# 8_imu_debug_conn.net
KiCad netlist of a schematic drawn in Altium Designer
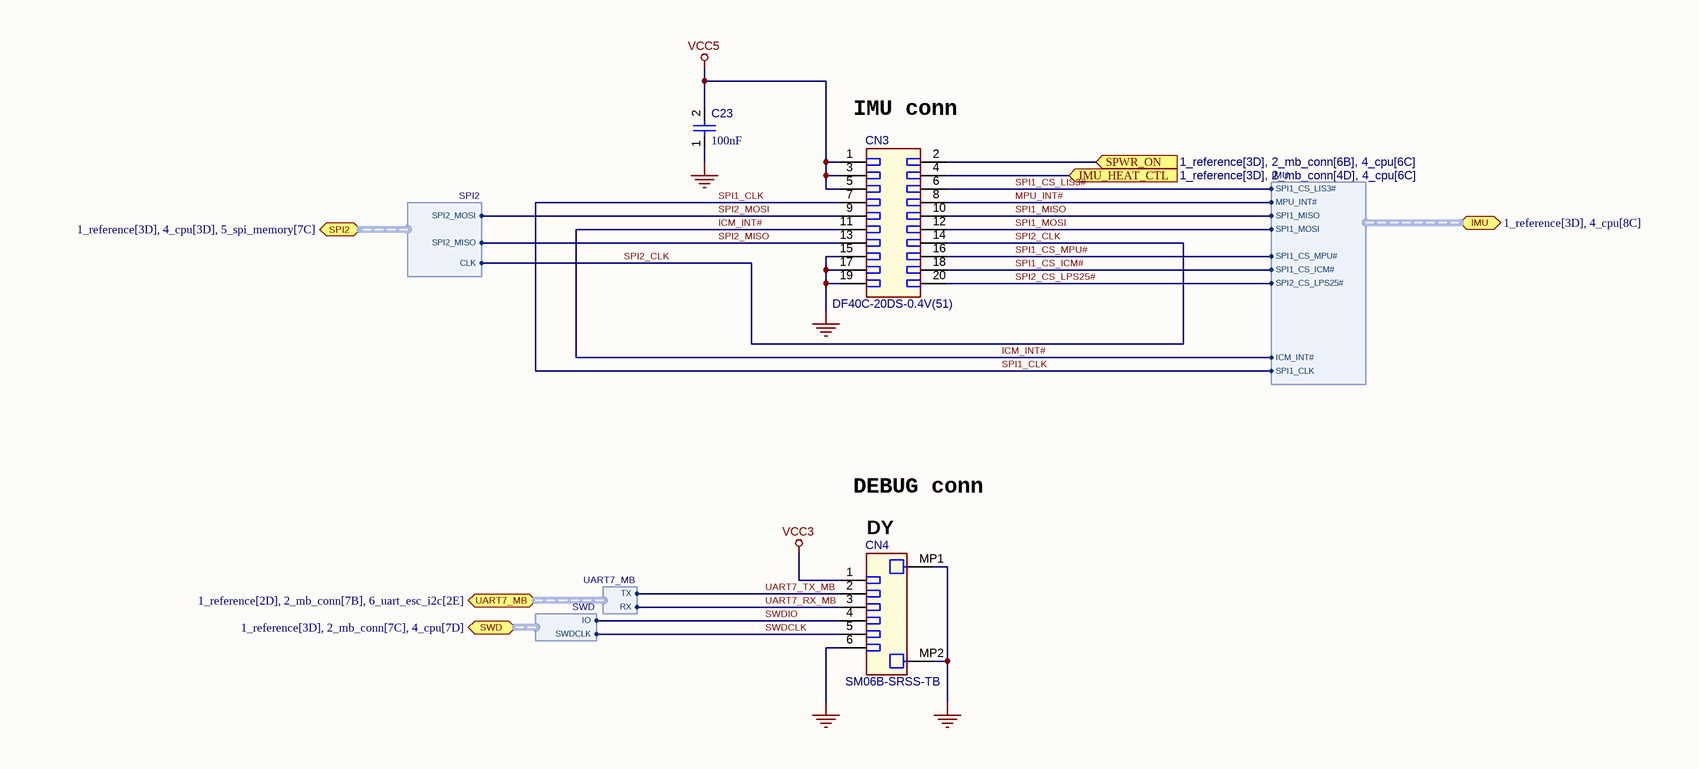
[diagram p0: 8_imu&debug_conn.SchDoc]

(export (version "E")
  (design (tool "Eeschema 10.0.6"))
  (components
    (comp (ref "C23")
      (value "100nF")
      (footprint "CAPC0402(1005)60_L")
      (description "Chip Capacitor, 100nF +/-20%, 10V, 0402, Thickness 0.6 mm")
      (fields (field (name "TOLERANCE") "20%") (field (name "Comment") "Capacitor 100nF +/-20% 10V 0402"))
      (libsource (lib "MHH -  Altium Advanced Course A365 01") (part "CAP-NP-2"))
    )
    (comp (ref "CN3")
      (value "DF40C-20DS-0.4V(51)")
      (footprint "HIRO-DF40C-20DS-0.4V(51)_V")
      (description "Receptacle Connector, 30 V, 0.3 A, -35 to 85 degC, RoHS, Tape and Reel")
      (libsource (lib "MHH -  Altium Advanced Course A365 01") (part "CMP-00114-7"))
    )
    (comp (ref "CN4")
      (value "SM06B-SRSS-TB")
      (footprint "JST-SM06B-SRSS-TB_V")
      (description "Male Header, Pitch 1 mm, 1 x 6 Position, Height 2.95 mm, -25 to 85 degC, RoHS, Tape and Reel")
      (libsource (lib "MHH -  Altium Advanced Course A365 01") (part "CMP-00143-5"))
    )
  )
  (nets
    (net (code "5") (name "/ICM_INT#") (class "Default")
      (node (ref "CN3") (pin "11") (pinfunction "11_11") (pintype "passive"))
    )
    (net (code "6") (name "/IMU_HEAT_CTL") (class "Default")
      (node (ref "CN3") (pin "4") (pinfunction "4_4") (pintype "passive"))
    )
    (net (code "7") (name "/MPU_INT#") (class "Default")
      (node (ref "CN3") (pin "8") (pinfunction "8_8") (pintype "passive"))
    )
    (net (code "8") (name "/SPI1_CLK") (class "Default")
      (node (ref "CN3") (pin "7") (pinfunction "7_7") (pintype "passive"))
    )
    (net (code "9") (name "/SPI1_CS_ICM#") (class "Default")
      (node (ref "CN3") (pin "18") (pinfunction "18_18") (pintype "passive"))
    )
    (net (code "10") (name "/SPI1_CS_LIS3#") (class "Default")
      (node (ref "CN3") (pin "6") (pinfunction "6_6") (pintype "passive"))
    )
    (net (code "11") (name "/SPI1_CS_MPU#") (class "Default")
      (node (ref "CN3") (pin "16") (pinfunction "16_16") (pintype "passive"))
    )
    (net (code "12") (name "/SPI1_MISO") (class "Default")
      (node (ref "CN3") (pin "10") (pinfunction "10_10") (pintype "passive"))
    )
    (net (code "13") (name "/SPI1_MOSI") (class "Default")
      (node (ref "CN3") (pin "12") (pinfunction "12_12") (pintype "passive"))
    )
    (net (code "14") (name "/SPI2_CLK") (class "Default")
      (node (ref "CN3") (pin "14") (pinfunction "14_14") (pintype "passive"))
    )
    (net (code "15") (name "/SPI2_CS_LPS25#") (class "Default")
      (node (ref "CN3") (pin "20") (pinfunction "20_20") (pintype "passive"))
    )
    (net (code "16") (name "/SPI2_MISO") (class "Default")
      (node (ref "CN3") (pin "13") (pinfunction "13_13") (pintype "passive"))
    )
    (net (code "17") (name "/SPI2_MOSI") (class "Default")
      (node (ref "CN3") (pin "9") (pinfunction "9_9") (pintype "passive"))
    )
    (net (code "18") (name "/SPWR_ON") (class "Default")
      (node (ref "CN3") (pin "2") (pinfunction "2_2") (pintype "passive"))
    )
    (net (code "19") (name "/SWDCLK") (class "Default")
      (node (ref "CN4") (pin "5") (pinfunction "5_5") (pintype "passive"))
    )
    (net (code "20") (name "/SWDIO") (class "Default")
      (node (ref "CN4") (pin "4") (pinfunction "4_4") (pintype "passive"))
    )
    (net (code "21") (name "/UART7_RX_MB") (class "Default")
      (node (ref "CN4") (pin "3") (pinfunction "3_3") (pintype "passive"))
    )
    (net (code "22") (name "/UART7_TX_MB") (class "Default")
      (node (ref "CN4") (pin "2") (pinfunction "2_2") (pintype "passive"))
    )
    (net (code "27") (name "GND") (class "Default")
      (node (ref "C23") (pin "1") (pinfunction "1_1") (pintype "passive"))
      (node (ref "CN3") (pin "15") (pinfunction "15_15") (pintype "passive"))
      (node (ref "CN3") (pin "17") (pinfunction "17_17") (pintype "passive"))
      (node (ref "CN3") (pin "19") (pinfunction "19_19") (pintype "passive"))
      (node (ref "CN4") (pin "6") (pinfunction "6_6") (pintype "passive"))
      (node (ref "CN4") (pin "MP1") (pinfunction "MP1_MP1") (pintype "passive"))
      (node (ref "CN4") (pin "MP2") (pinfunction "MP2_MP2") (pintype "passive"))
    )
    (net (code "28") (name "VCC3") (class "Default")
      (node (ref "CN4") (pin "1") (pinfunction "1_1") (pintype "passive"))
    )
    (net (code "29") (name "VCC5") (class "Default")
      (node (ref "C23") (pin "2") (pinfunction "2_2") (pintype "passive"))
      (node (ref "CN3") (pin "1") (pinfunction "1_1") (pintype "passive"))
      (node (ref "CN3") (pin "3") (pinfunction "3_3") (pintype "passive"))
      (node (ref "CN3") (pin "5") (pinfunction "5_5") (pintype "passive"))
    )
  )
)
